# USBasp.net
KiCad netlist of a schematic drawn in Altium Designer
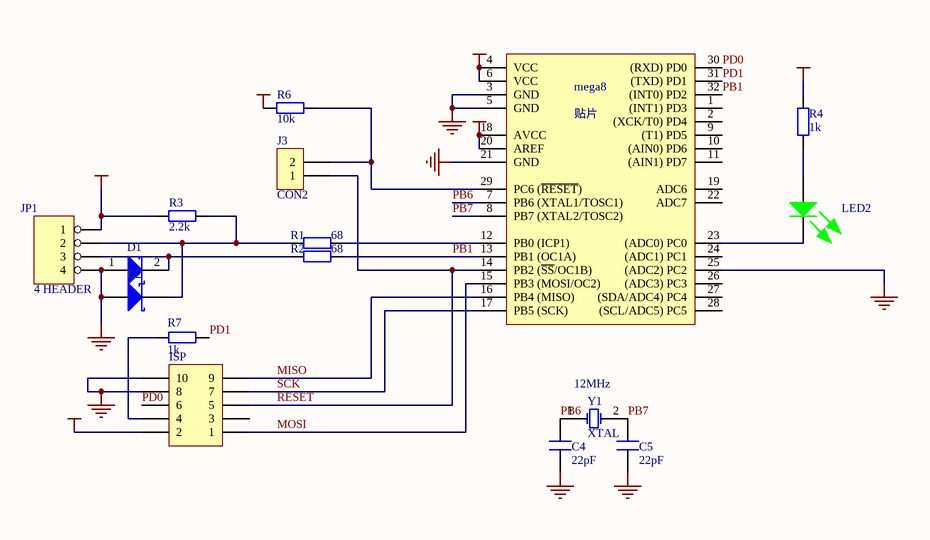
[diagram p0: USBasp_下载线.SchDoc]

(export (version "E")
  (design (tool "Eeschema 10.0.6"))
  (components
    (comp (ref "C4")
      (value "22pF")
      (footprint "TP-0805-R")
      (description "Capacitor SMD1206")
      (libsource (lib "*") (part "CAPSMD"))
    )
    (comp (ref "C5")
      (value "22pF")
      (footprint "TP-0805-R")
      (description "Capacitor SMD1206")
      (libsource (lib "*") (part "CAPSMD"))
    )
    (comp (ref "D1")
      (value "Diode 11DQ03")
      (footprint "TPDR")
      (description "Schottky Rectifier")
      (fields (field (name "PUBLISHER") "Altium Limited"))
      (libsource (lib "Miscellaneous Devices") (part "Diode 11DQ03"))
    )
    (comp (ref "D2")
      (value "Diode 11DQ03")
      (footprint "TPDR")
      (description "Schottky Rectifier")
      (fields (field (name "PUBLISHER") "Altium Limited"))
      (libsource (lib "") (part "Diode 11DQ03_1"))
    )
    (comp (ref "ISP")
      (value "~")
      (footprint "HDR2X5")
      (description "Header, 5-Pin, Dual row, Right Angle")
      (fields (field (name "MANUFACTURER") "Generic Components"))
      (libsource (lib "*") (part "MLW10A"))
    )
    (comp (ref "J3")
      (value "CON2")
      (footprint "HDR1X2")
      (description "Connector")
      (libsource (lib "*") (part "CON2"))
    )
    (comp (ref "JP1")
      (value "4 HEADER")
      (footprint "USB-5V")
      (description "4 Pin Header")
      (libsource (lib "*") (part "4 HEADER"))
    )
    (comp (ref "LED2")
      (value "~")
      (footprint "TP-0805-D")
      (description "Zöld Led 3mm")
      (libsource (lib "*") (part "LED Zöld"))
    )
    (comp (ref "mega8")
      (value "贴片")
      (footprint "QFP7x7-G32/N")
      (description "8 位微处理器/32引脚")
      (fields (field (name "发布者") "磊元工作室"))
      (libsource (lib "微控制处理器") (part "ATmega8-A"))
    )
    (comp (ref "R1")
      (value "68")
      (footprint "TP-0805-R")
      (description "Resistor SMD1206, 1% fémréteg")
      (libsource (lib "*") (part "RES"))
    )
    (comp (ref "R2")
      (value "68")
      (footprint "TP-0805-R")
      (description "Resistor SMD1206, 1% fémréteg")
      (libsource (lib "*") (part "RES"))
    )
    (comp (ref "R3")
      (value "2.2k")
      (footprint "TP-0805-R")
      (description "Resistor SMD1206, 1% fémréteg")
      (libsource (lib "*") (part "RES"))
    )
    (comp (ref "R4")
      (value "1k")
      (footprint "TP-0805-R")
      (description "Resistor SMD1206, 1% fémréteg")
      (libsource (lib "*") (part "RES"))
    )
    (comp (ref "R6")
      (value "10k")
      (footprint "TP-0805-R")
      (description "Resistor SMD1206, 1% fémréteg")
      (libsource (lib "*") (part "RES"))
    )
    (comp (ref "R7")
      (value "1k")
      (footprint "TP-0805-R")
      (description "Resistor SMD1206, 1% fémréteg")
      (libsource (lib "*") (part "RES"))
    )
    (comp (ref "Y1")
      (value "XTAL")
      (footprint "JZ_ZC")
      (description "Crystal Oscillator")
      (fields
        (field (name "MANUFACTURER") "Generic Components")
        (field (name "ALTIUM_VALUE") "12MHz")
        (field (name "PUBLISHER") "Altium Hobart Technology Centre")
      )
      (libsource (lib "*") (part "XTAL"))
    )
  )
  (nets
    (net (code "1") (name "/MISO") (class "Default")
      (node (ref "ISP") (pin "9") (pinfunction "9_9") (pintype "passive"))
      (node (ref "mega8") (pin "16") (pinfunction "PB4_(MISO)_16") (pintype "passive"))
    )
    (net (code "2") (name "/MOSI") (class "Default")
      (node (ref "ISP") (pin "1") (pinfunction "1_1") (pintype "passive"))
      (node (ref "mega8") (pin "15") (pinfunction "PB3_(MOSI/OC2)_15") (pintype "passive"))
    )
    (net (code "3") (name "/PB1") (class "Default")
      (node (ref "R2") (pin "1") (pinfunction "1_1") (pintype "passive"))
      (node (ref "mega8") (pin "13") (pinfunction "PB1_(OC1A)_13") (pintype "passive"))
      (node (ref "mega8") (pin "32") (pinfunction "(INT0)_PD2_32") (pintype "passive"))
    )
    (net (code "4") (name "/PB6") (class "Default")
      (node (ref "C4") (pin "2") (pinfunction "2_2") (pintype "passive"))
      (node (ref "Y1") (pin "1") (pinfunction "OSC1_1") (pintype "passive"))
      (node (ref "mega8") (pin "7") (pinfunction "PB6_(XTAL1/TOSC1)_7") (pintype "passive"))
    )
    (net (code "5") (name "/PB7") (class "Default")
      (node (ref "C5") (pin "2") (pinfunction "2_2") (pintype "passive"))
      (node (ref "Y1") (pin "2") (pinfunction "OSC2_2") (pintype "passive"))
      (node (ref "mega8") (pin "8") (pinfunction "PB7_(XTAL2/TOSC2)_8") (pintype "passive"))
    )
    (net (code "6") (name "/PD0") (class "Default")
      (node (ref "ISP") (pin "6") (pinfunction "6_6") (pintype "passive"))
      (node (ref "mega8") (pin "30") (pinfunction "(RXD)_PD0_30") (pintype "passive"))
    )
    (net (code "7") (name "/PD1") (class "Default")
      (node (ref "R7") (pin "2") (pinfunction "2_2") (pintype "passive"))
      (node (ref "mega8") (pin "31") (pinfunction "(TXD)_PD1_31") (pintype "passive"))
    )
    (net (code "8") (name "/RESET") (class "Default")
      (node (ref "ISP") (pin "5") (pinfunction "5_5") (pintype "passive"))
      (node (ref "J3") (pin "1") (pinfunction "1_1") (pintype "passive"))
      (node (ref "mega8") (pin "14") (pinfunction "PB2_(~{SS}/OC1B)_14") (pintype "passive"))
    )
    (net (code "9") (name "/SCK") (class "Default")
      (node (ref "ISP") (pin "7") (pinfunction "7_7") (pintype "passive"))
      (node (ref "mega8") (pin "17") (pinfunction "PB5_(SCK)_17") (pintype "passive"))
    )
    (net (code "10") (name "GND") (class "Default")
      (node (ref "C4") (pin "1") (pinfunction "1_1") (pintype "passive"))
      (node (ref "C5") (pin "1") (pinfunction "1_1") (pintype "passive"))
      (node (ref "D1") (pin "1") (pinfunction "A_1") (pintype "passive"))
      (node (ref "D2") (pin "1") (pinfunction "A_1") (pintype "passive"))
      (node (ref "ISP") (pin "10") (pinfunction "10_10") (pintype "passive"))
      (node (ref "ISP") (pin "8") (pinfunction "8_8") (pintype "passive"))
      (node (ref "JP1") (pin "4") (pinfunction "4_4") (pintype "passive"))
      (node (ref "mega8") (pin "21") (pinfunction "GND_21") (pintype "passive"))
      (node (ref "mega8") (pin "25") (pinfunction "(ADC2)_PC2_25") (pintype "passive"))
      (node (ref "mega8") (pin "3") (pinfunction "GND_3") (pintype "passive"))
      (node (ref "mega8") (pin "5") (pinfunction "GND_5") (pintype "passive"))
    )
    (net (code "11") (name "Net-(D1-K)") (class "Default")
      (node (ref "D1") (pin "2") (pinfunction "K_2") (pintype "passive"))
      (node (ref "JP1") (pin "3") (pinfunction "3_3") (pintype "passive"))
      (node (ref "R2") (pin "2") (pinfunction "2_2") (pintype "passive"))
    )
    (net (code "12") (name "Net-(D2-K)") (class "Default")
      (node (ref "D2") (pin "2") (pinfunction "K_2") (pintype "passive"))
      (node (ref "JP1") (pin "2") (pinfunction "2_2") (pintype "passive"))
      (node (ref "R1") (pin "1") (pinfunction "1_1") (pintype "passive"))
      (node (ref "R3") (pin "1") (pinfunction "1_1") (pintype "passive"))
    )
    (net (code "13") (name "Net-(ISP-Pad4)") (class "Default")
      (node (ref "ISP") (pin "4") (pinfunction "4_4") (pintype "passive"))
      (node (ref "R7") (pin "1") (pinfunction "1_1") (pintype "passive"))
    )
    (net (code "14") (name "Net-(LED2-Pad1)") (class "Default")
      (node (ref "LED2") (pin "1") (pinfunction "1_1") (pintype "passive"))
      (node (ref "R4") (pin "1") (pinfunction "1_1") (pintype "passive"))
    )
    (net (code "15") (name "Net-(mega8-(ADC0)_PC0)") (class "Default")
      (node (ref "LED2") (pin "2") (pinfunction "2_2") (pintype "passive"))
      (node (ref "mega8") (pin "23") (pinfunction "(ADC0)_PC0_23") (pintype "passive"))
    )
    (net (code "16") (name "Net-(mega8-PB0_(ICP1))") (class "Default")
      (node (ref "R1") (pin "2") (pinfunction "2_2") (pintype "passive"))
      (node (ref "mega8") (pin "12") (pinfunction "PB0_(ICP1)_12") (pintype "passive"))
    )
    (net (code "17") (name "Net-(mega8-PC6_(~{RESET}))") (class "Default")
      (node (ref "J3") (pin "2") (pinfunction "2_2") (pintype "passive"))
      (node (ref "R6") (pin "1") (pinfunction "1_1") (pintype "passive"))
      (node (ref "mega8") (pin "29") (pinfunction "PC6_(~{RESET})_29") (pintype "passive"))
    )
    (net (code "18") (name "VCC") (class "Default")
      (node (ref "ISP") (pin "2") (pinfunction "2_2") (pintype "passive"))
      (node (ref "JP1") (pin "1") (pinfunction "1_1") (pintype "passive"))
      (node (ref "R3") (pin "2") (pinfunction "2_2") (pintype "passive"))
      (node (ref "R4") (pin "2") (pinfunction "2_2") (pintype "passive"))
      (node (ref "R6") (pin "2") (pinfunction "2_2") (pintype "passive"))
      (node (ref "mega8") (pin "18") (pinfunction "AVCC_18") (pintype "passive"))
      (node (ref "mega8") (pin "20") (pinfunction "AREF_20") (pintype "passive"))
      (node (ref "mega8") (pin "4") (pinfunction "VCC_4") (pintype "passive"))
      (node (ref "mega8") (pin "6") (pinfunction "VCC_6") (pintype "passive"))
    )
    (net (code "19") (name "unconnected-(ISP-Pad3)") (class "Default")
      (node (ref "ISP") (pin "3") (pinfunction "3_3") (pintype "passive"))
    )
    (net (code "20") (name "unconnected-(mega8-(ADC1)_PC1-Pad24)") (class "Default")
      (node (ref "mega8") (pin "24") (pinfunction "(ADC1)_PC1_24") (pintype "passive"))
    )
    (net (code "21") (name "unconnected-(mega8-(ADC3)_PC3-Pad26)") (class "Default")
      (node (ref "mega8") (pin "26") (pinfunction "(ADC3)_PC3_26") (pintype "passive"))
    )
    (net (code "22") (name "unconnected-(mega8-(AIN0)_PD6-Pad10)") (class "Default")
      (node (ref "mega8") (pin "10") (pinfunction "(AIN0)_PD6_10") (pintype "passive"))
    )
    (net (code "23") (name "unconnected-(mega8-(AIN1)_PD7-Pad11)") (class "Default")
      (node (ref "mega8") (pin "11") (pinfunction "(AIN1)_PD7_11") (pintype "passive"))
    )
    (net (code "24") (name "unconnected-(mega8-(INT1)_PD3-Pad1)") (class "Default")
      (node (ref "mega8") (pin "1") (pinfunction "(INT1)_PD3_1") (pintype "passive"))
    )
    (net (code "25") (name "unconnected-(mega8-(SCL{slash}ADC5)_PC5-Pad28)") (class "Default")
      (node (ref "mega8") (pin "28") (pinfunction "(SCL/ADC5)_PC5_28") (pintype "passive"))
    )
    (net (code "26") (name "unconnected-(mega8-(SDA{slash}ADC4)_PC4-Pad27)") (class "Default")
      (node (ref "mega8") (pin "27") (pinfunction "(SDA/ADC4)_PC4_27") (pintype "passive"))
    )
    (net (code "27") (name "unconnected-(mega8-(T1)_PD5-Pad9)") (class "Default")
      (node (ref "mega8") (pin "9") (pinfunction "(T1)_PD5_9") (pintype "passive"))
    )
    (net (code "28") (name "unconnected-(mega8-(XCK{slash}T0)_PD4-Pad2)") (class "Default")
      (node (ref "mega8") (pin "2") (pinfunction "(XCK/T0)_PD4_2") (pintype "passive"))
    )
    (net (code "29") (name "unconnected-(mega8-ADC6-Pad19)") (class "Default")
      (node (ref "mega8") (pin "19") (pinfunction "ADC6_19") (pintype "passive"))
    )
    (net (code "30") (name "unconnected-(mega8-ADC7-Pad22)") (class "Default")
      (node (ref "mega8") (pin "22") (pinfunction "ADC7_22") (pintype "passive"))
    )
  )
)
